# mw_itb_full_v1_7_2.net
KiCad netlist of a schematic drawn in EAGLE
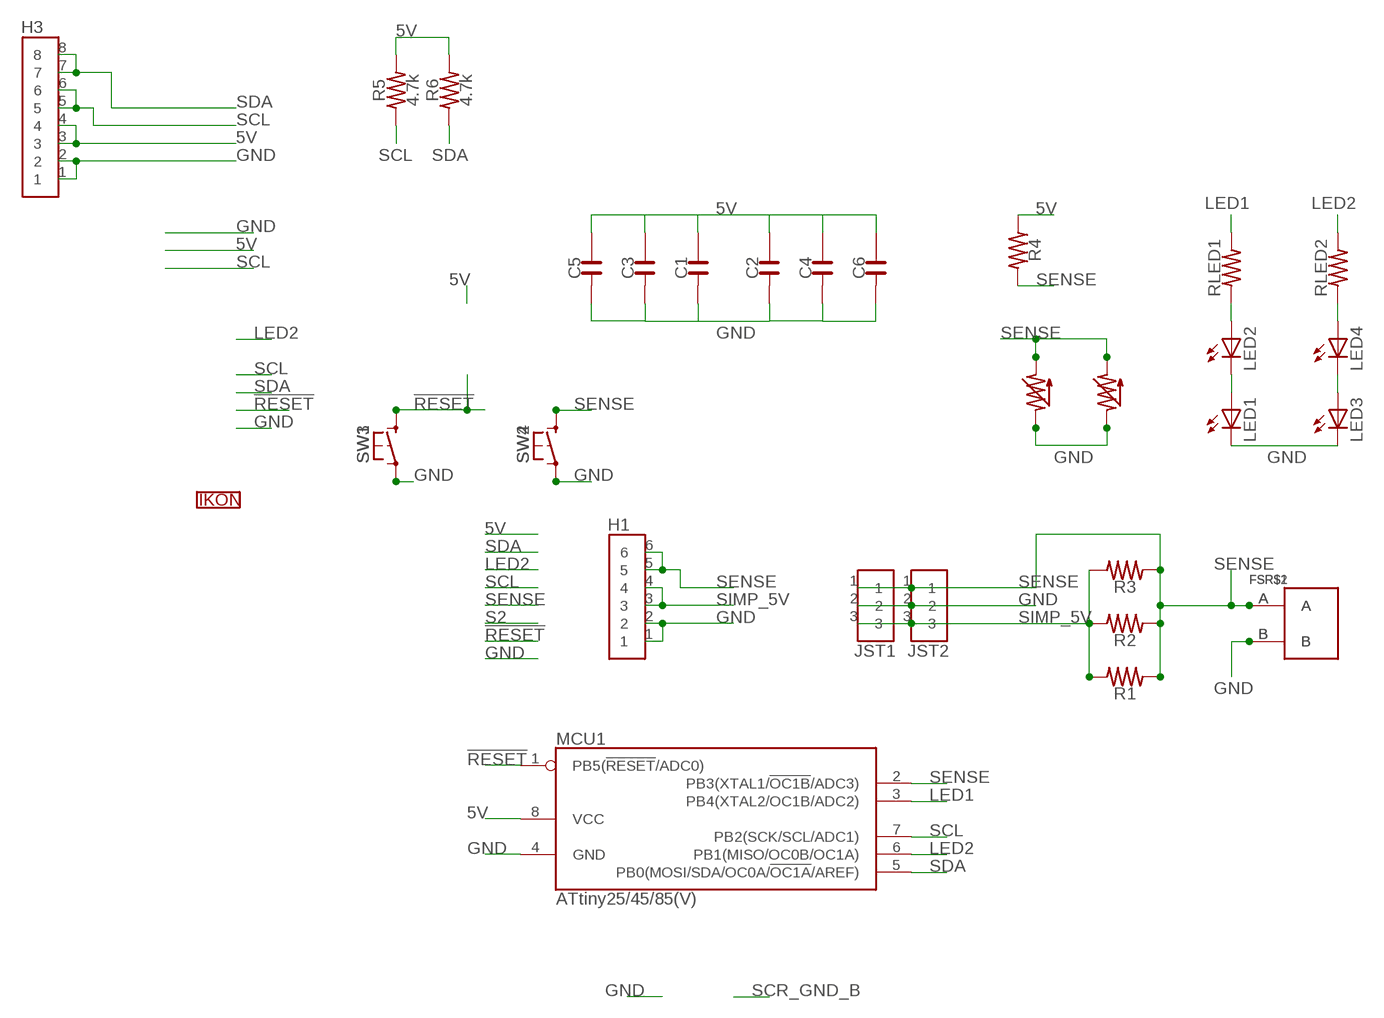
[diagram p0: schematic, sheet 1]

(export (version "E")
  (design (tool "Eeschema 10.0.6"))
  (components
    (comp (ref "C1")
      (value "CAPACITOR-1206")
      (footprint "eagle-import:1206_YAGEO")
      (libsource (lib "eagle-import") (part "CAPACITOR-1206"))
    )
    (comp (ref "C2")
      (value "CAPACITOR-1206")
      (footprint "eagle-import:1206_YAGEO")
      (libsource (lib "eagle-import") (part "CAPACITOR-1206"))
    )
    (comp (ref "C3")
      (value "CAPACITOR-0805")
      (footprint "eagle-import:0805_YAGEO")
      (libsource (lib "eagle-import") (part "CAPACITOR-0805"))
    )
    (comp (ref "C4")
      (value "CAPACITOR-0805")
      (footprint "eagle-import:0805_YAGEO")
      (libsource (lib "eagle-import") (part "CAPACITOR-0805"))
    )
    (comp (ref "C5")
      (value "CAPACITOR-0603")
      (footprint "eagle-import:0603_YAGEO")
      (libsource (lib "eagle-import") (part "CAPACITOR-0603"))
    )
    (comp (ref "C6")
      (value "CAPACITOR-0603")
      (footprint "eagle-import:0603_YAGEO")
      (libsource (lib "eagle-import") (part "CAPACITOR-0603"))
    )
    (comp (ref "FSR$1")
      (value "FSR_PAD88X44_P2B")
      (footprint "eagle-import:FSR_PAD_88X44_P2B")
      (libsource (lib "eagle-import") (part "FSR_PAD88X44_P2B"))
    )
    (comp (ref "FSR$2")
      (value "FSR_PAD88X44_P2B")
      (footprint "eagle-import:FSR_PAD_88X44_P2B")
      (libsource (lib "eagle-import") (part "FSR_PAD88X44_P2B"))
    )
    (comp (ref "H1")
      (value "HEADER_6P-0.1\"_2X3-SMD-SULLINS")
      (footprint "eagle-import:HEADER-0.1__2X3-SMD-SULLINS")
      (libsource (lib "eagle-import") (part "HEADER_6P-0.1{dblquote}_2X3-SMD-SULLINS"))
    )
    (comp (ref "H3")
      (value "HEADER_8P-0.1\"_2X4-SMD-SULLINS")
      (footprint "eagle-import:HEADER-0.1__2X4-SMD-SULLINS")
      (libsource (lib "eagle-import") (part "HEADER_8P-0.1{dblquote}_2X4-SMD-SULLINS"))
    )
    (comp (ref "JST1")
      (value "JST-3-PH-SMD-TOP")
      (footprint "eagle-import:JST_PH_SMD_3_TOP")
      (libsource (lib "eagle-import") (part "JST-3-PH-SMD-TOP"))
    )
    (comp (ref "JST2")
      (value "JST-3-PH-SMD-TOP")
      (footprint "eagle-import:JST_PH_SMD_3_TOP")
      (libsource (lib "eagle-import") (part "JST-3-PH-SMD-TOP"))
    )
    (comp (ref "LED1")
      (value "LED-ZBEND_RM")
      (footprint "eagle-import:Z-BEND_RM")
      (libsource (lib "eagle-import") (part "LED-ZBEND_RM"))
    )
    (comp (ref "LED2")
      (value "LED-ZBEND_RM")
      (footprint "eagle-import:Z-BEND_RM")
      (libsource (lib "eagle-import") (part "LED-ZBEND_RM"))
    )
    (comp (ref "LED3")
      (value "LED-ZBEND_RM")
      (footprint "eagle-import:Z-BEND_RM")
      (libsource (lib "eagle-import") (part "LED-ZBEND_RM"))
    )
    (comp (ref "LED4")
      (value "LED-ZBEND_RM")
      (footprint "eagle-import:Z-BEND_RM")
      (libsource (lib "eagle-import") (part "LED-ZBEND_RM"))
    )
    (comp (ref "MCU1")
      (value "ATMEL_ATTINY25/45/85(V)-SOIC_DUAL")
      (footprint "eagle-import:SOIC-8_DUAL")
      (libsource (lib "eagle-import") (part "ATMEL_ATTINY25/45/85(V)-SOIC_DUAL"))
    )
    (comp (ref "R1")
      (value "RESISTOR-1206")
      (footprint "eagle-import:1206_YAGEO")
      (libsource (lib "eagle-import") (part "RESISTOR-1206"))
    )
    (comp (ref "R2")
      (value "RESISTOR-0805")
      (footprint "eagle-import:0805_YAGEO")
      (libsource (lib "eagle-import") (part "RESISTOR-0805"))
    )
    (comp (ref "R3")
      (value "RESISTOR-0603")
      (footprint "eagle-import:0603_YAGEO")
      (libsource (lib "eagle-import") (part "RESISTOR-0603"))
    )
    (comp (ref "R4")
      (value "RESISTOR-0603")
      (footprint "eagle-import:0603_YAGEO")
      (libsource (lib "eagle-import") (part "RESISTOR-0603"))
    )
    (comp (ref "R5")
      (value "4.7k")
      (footprint "eagle-import:0603_YAGEO")
      (libsource (lib "eagle-import") (part "RESISTOR-0603"))
    )
    (comp (ref "R6")
      (value "4.7k")
      (footprint "eagle-import:0603_YAGEO")
      (libsource (lib "eagle-import") (part "RESISTOR-0603"))
    )
    (comp (ref "RLED1")
      (value "RESISTOR-0603")
      (footprint "eagle-import:0603_YAGEO")
      (libsource (lib "eagle-import") (part "RESISTOR-0603"))
    )
    (comp (ref "RLED2")
      (value "RESISTOR-0603")
      (footprint "eagle-import:0603_YAGEO")
      (libsource (lib "eagle-import") (part "RESISTOR-0603"))
    )
    (comp (ref "SW1")
      (value "SWITCH_SPST-KMT0")
      (footprint "eagle-import:SWITCH_KMT0")
      (libsource (lib "eagle-import") (part "SWITCH_SPST-KMT0"))
    )
    (comp (ref "SW2")
      (value "SWITCH_SPST-KMT0")
      (footprint "eagle-import:SWITCH_KMT0")
      (libsource (lib "eagle-import") (part "SWITCH_SPST-KMT0"))
    )
    (comp (ref "SW3")
      (value "SWITCH_SPST-TL3315")
      (footprint "eagle-import:SWITCH_TL3315")
      (libsource (lib "eagle-import") (part "SWITCH_SPST-TL3315"))
    )
    (comp (ref "SW4")
      (value "SWITCH_SPST-TL3315")
      (footprint "eagle-import:SWITCH_TL3315")
      (libsource (lib "eagle-import") (part "SWITCH_SPST-TL3315"))
    )
    (comp (ref "U$1")
      (value "FSR_PINS")
      (footprint "eagle-import:FSR_0.1_-PITCH_PADS-0.05_X0.5_")
      (libsource (lib "eagle-import") (part "FSR_PINSJUMBO_SMD"))
    )
    (comp (ref "U$2")
      (value "FSR_PLACE")
      (footprint "eagle-import:FSR_1.5[IN]_SQR")
      (libsource (lib "eagle-import") (part "FSR_PLACE1.5{dblquote}SQR"))
    )
    (comp (ref "U$3")
      (value "FSR_PINS")
      (footprint "eagle-import:FSR_0.1_-PITCH_PADS-0.05_X0.5_")
      (libsource (lib "eagle-import") (part "FSR_PINSJUMBO_SMD"))
    )
    (comp (ref "U$4")
      (value "FSR_PLACE")
      (footprint "eagle-import:FSR_1.5[IN]_SQR")
      (libsource (lib "eagle-import") (part "FSR_PLACE1.5{dblquote}SQR"))
    )
    (comp (ref "U$5")
      (value "FSR_PLACE")
      (footprint "eagle-import:FSR_1.5[IN]_SQR")
      (libsource (lib "eagle-import") (part "FSR_PLACE1.5{dblquote}SQR"))
    )
    (comp (ref "U$6")
      (value "FSR_PLACE")
      (footprint "eagle-import:FSR_1.5[IN]_SQR")
      (libsource (lib "eagle-import") (part "FSR_PLACE1.5{dblquote}SQR"))
    )
    (comp (ref "U$9")
      (value "FSR_PINS")
      (footprint "eagle-import:FSR_0.1_-PITCH_PADS-0.05_X0.5_")
      (libsource (lib "eagle-import") (part "FSR_PINSJUMBO_SMD"))
    )
    (comp (ref "U$10")
      (value "FSR_PINS")
      (footprint "eagle-import:FSR_0.1_-PITCH_PADS-0.05_X0.5_")
      (libsource (lib "eagle-import") (part "FSR_PINSJUMBO_SMD"))
    )
    (comp (ref "U$11")
      (value "IKONLEARNING-20MIL")
      (footprint "eagle-import:IKON_LEARNING_20MIL")
      (libsource (lib "eagle-import") (part "IKONLEARNING-20MIL"))
    )
  )
  (nets
    (net (code "1") (name "/5V") (class "Default")
      (node (ref "C1") (pin "2") (pinfunction "P$2_2") (pintype "passive"))
      (node (ref "C2") (pin "2") (pinfunction "P$2_2") (pintype "passive"))
      (node (ref "C3") (pin "2") (pinfunction "P$2_2") (pintype "passive"))
      (node (ref "C4") (pin "2") (pinfunction "P$2_2") (pintype "passive"))
      (node (ref "C5") (pin "2") (pinfunction "P$2_2") (pintype "passive"))
      (node (ref "C6") (pin "2") (pinfunction "P$2_2") (pintype "passive"))
      (node (ref "H3") (pin "3") (pinfunction "3_3") (pintype "bidirectional"))
      (node (ref "H3") (pin "4") (pinfunction "4_4") (pintype "bidirectional"))
      (node (ref "MCU1") (pin "8") (pinfunction "VCC_8") (pintype "bidirectional"))
      (node (ref "R4") (pin "1") (pinfunction "1_1") (pintype "passive"))
      (node (ref "R5") (pin "2") (pinfunction "2_2") (pintype "passive"))
      (node (ref "R6") (pin "2") (pinfunction "2_2") (pintype "passive"))
    )
    (net (code "2") (name "/GND") (class "Default")
      (node (ref "C1") (pin "1") (pinfunction "P$1_1") (pintype "passive"))
      (node (ref "C2") (pin "1") (pinfunction "P$1_1") (pintype "passive"))
      (node (ref "C3") (pin "1") (pinfunction "P$1_1") (pintype "passive"))
      (node (ref "C4") (pin "1") (pinfunction "P$1_1") (pintype "passive"))
      (node (ref "C5") (pin "1") (pinfunction "P$1_1") (pintype "passive"))
      (node (ref "C6") (pin "1") (pinfunction "P$1_1") (pintype "passive"))
      (node (ref "FSR$1") (pin "B") (pinfunction "B_B") (pintype "bidirectional"))
      (node (ref "FSR$2") (pin "B") (pinfunction "B_B") (pintype "bidirectional"))
      (node (ref "H1") (pin "1") (pinfunction "1_1") (pintype "bidirectional"))
      (node (ref "H1") (pin "2") (pinfunction "2_2") (pintype "bidirectional"))
      (node (ref "H3") (pin "1") (pinfunction "1_1") (pintype "bidirectional"))
      (node (ref "H3") (pin "2") (pinfunction "2_2") (pintype "bidirectional"))
      (node (ref "JST1") (pin "2") (pinfunction "2_2") (pintype "bidirectional"))
      (node (ref "JST2") (pin "2") (pinfunction "2_2") (pintype "bidirectional"))
      (node (ref "LED1") (pin "K") (pinfunction "C_K") (pintype "passive"))
      (node (ref "LED3") (pin "K") (pinfunction "C_K") (pintype "passive"))
      (node (ref "MCU1") (pin "4") (pinfunction "GND_4") (pintype "bidirectional"))
      (node (ref "SW1") (pin "2@1") (pinfunction "2_2@1") (pintype "passive"))
      (node (ref "SW1") (pin "2@2") (pinfunction "2_2@2") (pintype "passive"))
      (node (ref "SW2") (pin "2@1") (pinfunction "2_2@1") (pintype "passive"))
      (node (ref "SW2") (pin "2@2") (pinfunction "2_2@2") (pintype "passive"))
      (node (ref "SW3") (pin "2@1") (pinfunction "2_2@1") (pintype "passive"))
      (node (ref "SW3") (pin "2@2") (pinfunction "2_2@2") (pintype "passive"))
      (node (ref "SW4") (pin "2@1") (pinfunction "2_2@1") (pintype "passive"))
      (node (ref "SW4") (pin "2@2") (pinfunction "2_2@2") (pintype "passive"))
      (node (ref "U$1") (pin "P$1") (pinfunction "P$1_P$1") (pintype "bidirectional"))
      (node (ref "U$10") (pin "P$1") (pinfunction "P$1_P$1") (pintype "bidirectional"))
      (node (ref "U$3") (pin "P$2") (pinfunction "P$2_P$2") (pintype "bidirectional"))
      (node (ref "U$9") (pin "P$2") (pinfunction "P$2_P$2") (pintype "bidirectional"))
    )
    (net (code "3") (name "/LED1") (class "Default")
      (node (ref "MCU1") (pin "3") (pinfunction "PB4(XTAL2/OC1B/ADC2)_3") (pintype "bidirectional"))
      (node (ref "RLED1") (pin "2") (pinfunction "2_2") (pintype "passive"))
    )
    (net (code "4") (name "/LED2") (class "Default")
      (node (ref "MCU1") (pin "6") (pinfunction "PB1(MISO/OC0B/OC1A)_6") (pintype "bidirectional"))
      (node (ref "RLED2") (pin "2") (pinfunction "2_2") (pintype "passive"))
    )
    (net (code "6") (name "/SCL") (class "Default")
      (node (ref "H3") (pin "5") (pinfunction "5_5") (pintype "bidirectional"))
      (node (ref "H3") (pin "6") (pinfunction "6_6") (pintype "bidirectional"))
      (node (ref "MCU1") (pin "7") (pinfunction "PB2(SCK/SCL/ADC1)_7") (pintype "bidirectional"))
      (node (ref "R5") (pin "1") (pinfunction "1_1") (pintype "passive"))
    )
    (net (code "8") (name "/SDA") (class "Default")
      (node (ref "H3") (pin "7") (pinfunction "7_7") (pintype "bidirectional"))
      (node (ref "H3") (pin "8") (pinfunction "8_8") (pintype "bidirectional"))
      (node (ref "MCU1") (pin "5") (pinfunction "PB0(MOSI/SDA/OC0A/~{OC1A}/AREF)_5") (pintype "bidirectional"))
      (node (ref "R6") (pin "1") (pinfunction "1_1") (pintype "passive"))
    )
    (net (code "9") (name "/SENSE") (class "Default")
      (node (ref "FSR$1") (pin "A") (pinfunction "A_A") (pintype "bidirectional"))
      (node (ref "FSR$2") (pin "A") (pinfunction "A_A") (pintype "bidirectional"))
      (node (ref "H1") (pin "5") (pinfunction "5_5") (pintype "bidirectional"))
      (node (ref "H1") (pin "6") (pinfunction "6_6") (pintype "bidirectional"))
      (node (ref "JST1") (pin "1") (pinfunction "1_1") (pintype "bidirectional"))
      (node (ref "JST2") (pin "1") (pinfunction "1_1") (pintype "bidirectional"))
      (node (ref "MCU1") (pin "2") (pinfunction "PB3(XTAL1/~{OC1B}/ADC3)_2") (pintype "bidirectional"))
      (node (ref "R1") (pin "1") (pinfunction "1_1") (pintype "passive"))
      (node (ref "R2") (pin "1") (pinfunction "1_1") (pintype "passive"))
      (node (ref "R3") (pin "1") (pinfunction "1_1") (pintype "passive"))
      (node (ref "R4") (pin "2") (pinfunction "2_2") (pintype "passive"))
      (node (ref "SW2") (pin "1@1") (pinfunction "1_1@1") (pintype "passive"))
      (node (ref "SW2") (pin "1@2") (pinfunction "1_1@2") (pintype "passive"))
      (node (ref "SW4") (pin "1@1") (pinfunction "1_1@1") (pintype "passive"))
      (node (ref "SW4") (pin "1@2") (pinfunction "1_1@2") (pintype "passive"))
      (node (ref "U$1") (pin "P$2") (pinfunction "P$2_P$2") (pintype "bidirectional"))
      (node (ref "U$10") (pin "P$2") (pinfunction "P$2_P$2") (pintype "bidirectional"))
      (node (ref "U$3") (pin "P$1") (pinfunction "P$1_P$1") (pintype "bidirectional"))
      (node (ref "U$9") (pin "P$1") (pinfunction "P$1_P$1") (pintype "bidirectional"))
    )
    (net (code "10") (name "/SIMP_5V") (class "Default")
      (node (ref "H1") (pin "3") (pinfunction "3_3") (pintype "bidirectional"))
      (node (ref "H1") (pin "4") (pinfunction "4_4") (pintype "bidirectional"))
      (node (ref "JST1") (pin "3") (pinfunction "3_3") (pintype "bidirectional"))
      (node (ref "JST2") (pin "3") (pinfunction "3_3") (pintype "bidirectional"))
      (node (ref "R1") (pin "2") (pinfunction "2_2") (pintype "passive"))
      (node (ref "R2") (pin "2") (pinfunction "2_2") (pintype "passive"))
      (node (ref "R3") (pin "2") (pinfunction "2_2") (pintype "passive"))
    )
    (net (code "11") (name "/~{RESET}") (class "Default")
      (node (ref "MCU1") (pin "1") (pinfunction "PB5(~{RESET}/ADC0)_1") (pintype "bidirectional"))
      (node (ref "SW1") (pin "1@1") (pinfunction "1_1@1") (pintype "passive"))
      (node (ref "SW1") (pin "1@2") (pinfunction "1_1@2") (pintype "passive"))
      (node (ref "SW3") (pin "1@1") (pinfunction "1_1@1") (pintype "passive"))
      (node (ref "SW3") (pin "1@2") (pinfunction "1_1@2") (pintype "passive"))
    )
    (net (code "12") (name "Net-(LED2-C)") (class "Default")
      (node (ref "LED1") (pin "A") (pinfunction "A_A") (pintype "passive"))
      (node (ref "LED2") (pin "K") (pinfunction "C_K") (pintype "passive"))
    )
    (net (code "13") (name "Net-(LED2-PadA)") (class "Default")
      (node (ref "LED2") (pin "A") (pinfunction "A_A") (pintype "passive"))
      (node (ref "RLED1") (pin "1") (pinfunction "1_1") (pintype "passive"))
    )
    (net (code "14") (name "Net-(LED4-C)") (class "Default")
      (node (ref "LED3") (pin "A") (pinfunction "A_A") (pintype "passive"))
      (node (ref "LED4") (pin "K") (pinfunction "C_K") (pintype "passive"))
    )
    (net (code "15") (name "Net-(LED4-PadA)") (class "Default")
      (node (ref "LED4") (pin "A") (pinfunction "A_A") (pintype "passive"))
      (node (ref "RLED2") (pin "1") (pinfunction "1_1") (pintype "passive"))
    )
  )
)
